# MotorDriverSchmv1.net
KiCad netlist of a schematic drawn in Altium Designer
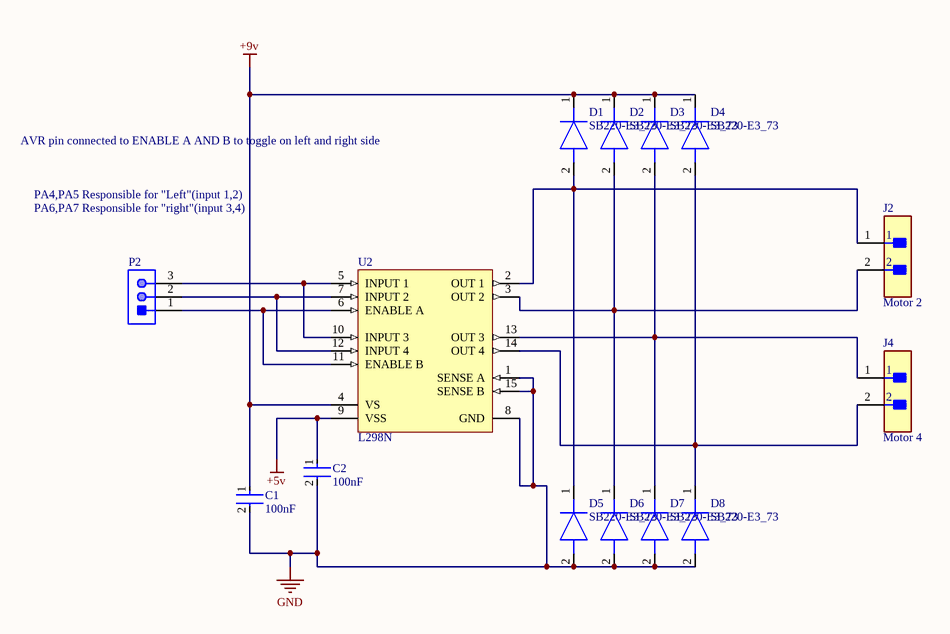
[diagram p0: MotorDriverSchmv1.SchDoc]

(export (version "E")
  (design (tool "Eeschema 10.0.6"))
  (components
    (comp (ref "C1")
      (value "100nF")
      (footprint "FP-K15H5-MFG")
      (description "CAP CER 0.1UF 50V X7R RADIAL")
      (fields (field (name "TOLERANCE") "10%") (field (name "VOLTAGE") "50V"))
      (libsource (lib "Altium Content Vault") (part "02cd4be3c70576c341d710602a673aa"))
    )
    (comp (ref "C2")
      (value "100nF")
      (footprint "FP-K15H5-MFG")
      (description "CAP CER 0.1UF 50V X7R RADIAL")
      (fields (field (name "TOLERANCE") "10%") (field (name "VOLTAGE") "50V"))
      (libsource (lib "Altium Content Vault") (part "02cd4be3c70576c341d710602a673aa"))
    )
    (comp (ref "D1")
      (value "SB220-E3_73")
      (footprint "SamacSys:DIOAD1910W86L670D310")
      (description "Diode")
      (fields
        (field (name "MANUFACTURER_PART_NUMBER") "SB220-E3/73")
        (field (name "MOUSER PART NUMBER") "625-SB220-E3/73")
      )
      (libsource (lib "*") (part "SB220-E3_73"))
    )
    (comp (ref "D2")
      (value "SB220-E3_73")
      (footprint "SamacSys:DIOAD1910W86L670D310")
      (description "Diode")
      (fields
        (field (name "MANUFACTURER_PART_NUMBER") "SB220-E3/73")
        (field (name "MOUSER PART NUMBER") "625-SB220-E3/73")
      )
      (libsource (lib "*") (part "SB220-E3_73"))
    )
    (comp (ref "D3")
      (value "SB220-E3_73")
      (footprint "SamacSys:DIOAD1910W86L670D310")
      (description "Diode")
      (fields
        (field (name "MANUFACTURER_PART_NUMBER") "SB220-E3/73")
        (field (name "MOUSER PART NUMBER") "625-SB220-E3/73")
      )
      (libsource (lib "*") (part "SB220-E3_73"))
    )
    (comp (ref "D4")
      (value "SB220-E3_73")
      (footprint "SamacSys:DIOAD1910W86L670D310")
      (description "Diode")
      (fields
        (field (name "MANUFACTURER_PART_NUMBER") "SB220-E3/73")
        (field (name "MOUSER PART NUMBER") "625-SB220-E3/73")
      )
      (libsource (lib "*") (part "SB220-E3_73"))
    )
    (comp (ref "D5")
      (value "SB220-E3_73")
      (footprint "SamacSys:DIOAD1910W86L670D310")
      (description "Diode")
      (fields
        (field (name "MANUFACTURER_PART_NUMBER") "SB220-E3/73")
        (field (name "MOUSER PART NUMBER") "625-SB220-E3/73")
      )
      (libsource (lib "*") (part "SB220-E3_73"))
    )
    (comp (ref "D6")
      (value "SB220-E3_73")
      (footprint "SamacSys:DIOAD1910W86L670D310")
      (description "Diode")
      (fields
        (field (name "MANUFACTURER_PART_NUMBER") "SB220-E3/73")
        (field (name "MOUSER PART NUMBER") "625-SB220-E3/73")
      )
      (libsource (lib "*") (part "SB220-E3_73"))
    )
    (comp (ref "D7")
      (value "SB220-E3_73")
      (footprint "SamacSys:DIOAD1910W86L670D310")
      (description "Diode")
      (fields
        (field (name "MANUFACTURER_PART_NUMBER") "SB220-E3/73")
        (field (name "MOUSER PART NUMBER") "625-SB220-E3/73")
      )
      (libsource (lib "*") (part "SB220-E3_73"))
    )
    (comp (ref "D8")
      (value "SB220-E3_73")
      (footprint "SamacSys:DIOAD1910W86L670D310")
      (description "Diode")
      (fields
        (field (name "MANUFACTURER_PART_NUMBER") "SB220-E3/73")
        (field (name "MOUSER PART NUMBER") "625-SB220-E3/73")
      )
      (libsource (lib "*") (part "SB220-E3_73"))
    )
    (comp (ref "J2")
      (value "Motor 2")
      (footprint "FP-M20-9990246-MFG")
      (description "CONN HEADER VERT 2POS 2.54MM")
      (fields
        (field (name "OCTOPART") "https://octopart.com/m20-9990246-harwin-2590635")
        (field (name "MANUFACTURER") "Harwin")
      )
      (libsource (lib "Altium Content Vault") (part "3bc925449376181038e59eaffc5286c"))
    )
    (comp (ref "J4")
      (value "Motor 4")
      (footprint "FP-M20-9990246-MFG")
      (description "CONN HEADER VERT 2POS 2.54MM")
      (fields
        (field (name "OCTOPART") "https://octopart.com/m20-9990246-harwin-2590635")
        (field (name "MANUFACTURER") "Harwin")
      )
      (libsource (lib "Altium Content Vault") (part "3bc925449376181038e59eaffc5286c"))
    )
    (comp (ref "P2")
      (value "~")
      (footprint "MOLX-22-28-4033_V")
      (description "Male Header, Pitch 2.54 mm, 1 x 3 Position, Height 8.38 mm, Tail Length 3.18 mm, RoHS, Bulk")
      (fields (field (name "MANUFACTURER") "Molex"))
      (libsource (lib "Altium Content Vault") (part "CN-1P-M-R3"))
    )
    (comp (ref "U2")
      (value "L298N")
      (footprint "STM-FM-15")
      (description "Dual Full-Bridge Driver, 4.8 to 46 V, -40 to 150 degC, 15-Pin FM (MW 15L), RoHS, Tube")
      (fields (field (name "MANUFACTURER") "STMicroelectronics") (field (name "PARTNUMBER") "L298"))
      (libsource (lib "Altium Content Vault") (part "STM-L298-15"))
    )
  )
  (nets
    (net (code "1") (name "+5v") (class "Default")
      (node (ref "C2") (pin "1") (pinfunction "1_1") (pintype "passive"))
      (node (ref "U2") (pin "9") (pinfunction "VSS_9") (pintype "power_in"))
    )
    (net (code "2") (name "+9v") (class "Default")
      (node (ref "C1") (pin "1") (pinfunction "1_1") (pintype "passive"))
      (node (ref "D1") (pin "1") (pinfunction "K_1") (pintype "passive"))
      (node (ref "D2") (pin "1") (pinfunction "K_1") (pintype "passive"))
      (node (ref "D3") (pin "1") (pinfunction "K_1") (pintype "passive"))
      (node (ref "D4") (pin "1") (pinfunction "K_1") (pintype "passive"))
      (node (ref "U2") (pin "4") (pinfunction "VS_4") (pintype "power_in"))
    )
    (net (code "3") (name "GND") (class "Default")
      (node (ref "C1") (pin "2") (pinfunction "2_2") (pintype "passive"))
      (node (ref "C2") (pin "2") (pinfunction "2_2") (pintype "passive"))
      (node (ref "D5") (pin "2") (pinfunction "A_2") (pintype "passive"))
      (node (ref "D6") (pin "2") (pinfunction "A_2") (pintype "passive"))
      (node (ref "D7") (pin "2") (pinfunction "A_2") (pintype "passive"))
      (node (ref "D8") (pin "2") (pinfunction "A_2") (pintype "passive"))
      (node (ref "U2") (pin "1") (pinfunction "SENSE_A_1") (pintype "input"))
      (node (ref "U2") (pin "15") (pinfunction "SENSE_B_15") (pintype "input"))
      (node (ref "U2") (pin "8") (pinfunction "GND_8") (pintype "power_in"))
    )
    (net (code "4") (name "Net-(D1-A)") (class "Default")
      (node (ref "D1") (pin "2") (pinfunction "A_2") (pintype "passive"))
      (node (ref "D5") (pin "1") (pinfunction "K_1") (pintype "passive"))
      (node (ref "J2") (pin "1") (pinfunction "1_1") (pintype "passive"))
      (node (ref "U2") (pin "2") (pinfunction "OUT_1_2") (pintype "output"))
    )
    (net (code "5") (name "Net-(D2-A)") (class "Default")
      (node (ref "D2") (pin "2") (pinfunction "A_2") (pintype "passive"))
      (node (ref "D6") (pin "1") (pinfunction "K_1") (pintype "passive"))
      (node (ref "J2") (pin "2") (pinfunction "2_2") (pintype "passive"))
      (node (ref "U2") (pin "3") (pinfunction "OUT_2_3") (pintype "output"))
    )
    (net (code "6") (name "Net-(D3-A)") (class "Default")
      (node (ref "D3") (pin "2") (pinfunction "A_2") (pintype "passive"))
      (node (ref "D7") (pin "1") (pinfunction "K_1") (pintype "passive"))
      (node (ref "J4") (pin "1") (pinfunction "1_1") (pintype "passive"))
      (node (ref "U2") (pin "13") (pinfunction "OUT_3_13") (pintype "output"))
    )
    (net (code "7") (name "Net-(D4-A)") (class "Default")
      (node (ref "D4") (pin "2") (pinfunction "A_2") (pintype "passive"))
      (node (ref "D8") (pin "1") (pinfunction "K_1") (pintype "passive"))
      (node (ref "J4") (pin "2") (pinfunction "2_2") (pintype "passive"))
      (node (ref "U2") (pin "14") (pinfunction "OUT_4_14") (pintype "output"))
    )
    (net (code "8") (name "Net-(U2-ENABLE_A)") (class "Default")
      (node (ref "P2") (pin "1") (pinfunction "1_1") (pintype "passive"))
      (node (ref "U2") (pin "11") (pinfunction "ENABLE_B_11") (pintype "input"))
      (node (ref "U2") (pin "6") (pinfunction "ENABLE_A_6") (pintype "input"))
    )
    (net (code "9") (name "Net-(U2-INPUT_1)") (class "Default")
      (node (ref "P2") (pin "3") (pinfunction "3_3") (pintype "passive"))
      (node (ref "U2") (pin "10") (pinfunction "INPUT_3_10") (pintype "input"))
      (node (ref "U2") (pin "5") (pinfunction "INPUT_1_5") (pintype "input"))
    )
    (net (code "10") (name "Net-(U2-INPUT_2)") (class "Default")
      (node (ref "P2") (pin "2") (pinfunction "2_2") (pintype "passive"))
      (node (ref "U2") (pin "12") (pinfunction "INPUT_4_12") (pintype "input"))
      (node (ref "U2") (pin "7") (pinfunction "INPUT_2_7") (pintype "input"))
    )
  )
)
